# Ethernet.net
KiCad netlist of a schematic drawn in Altium Designer
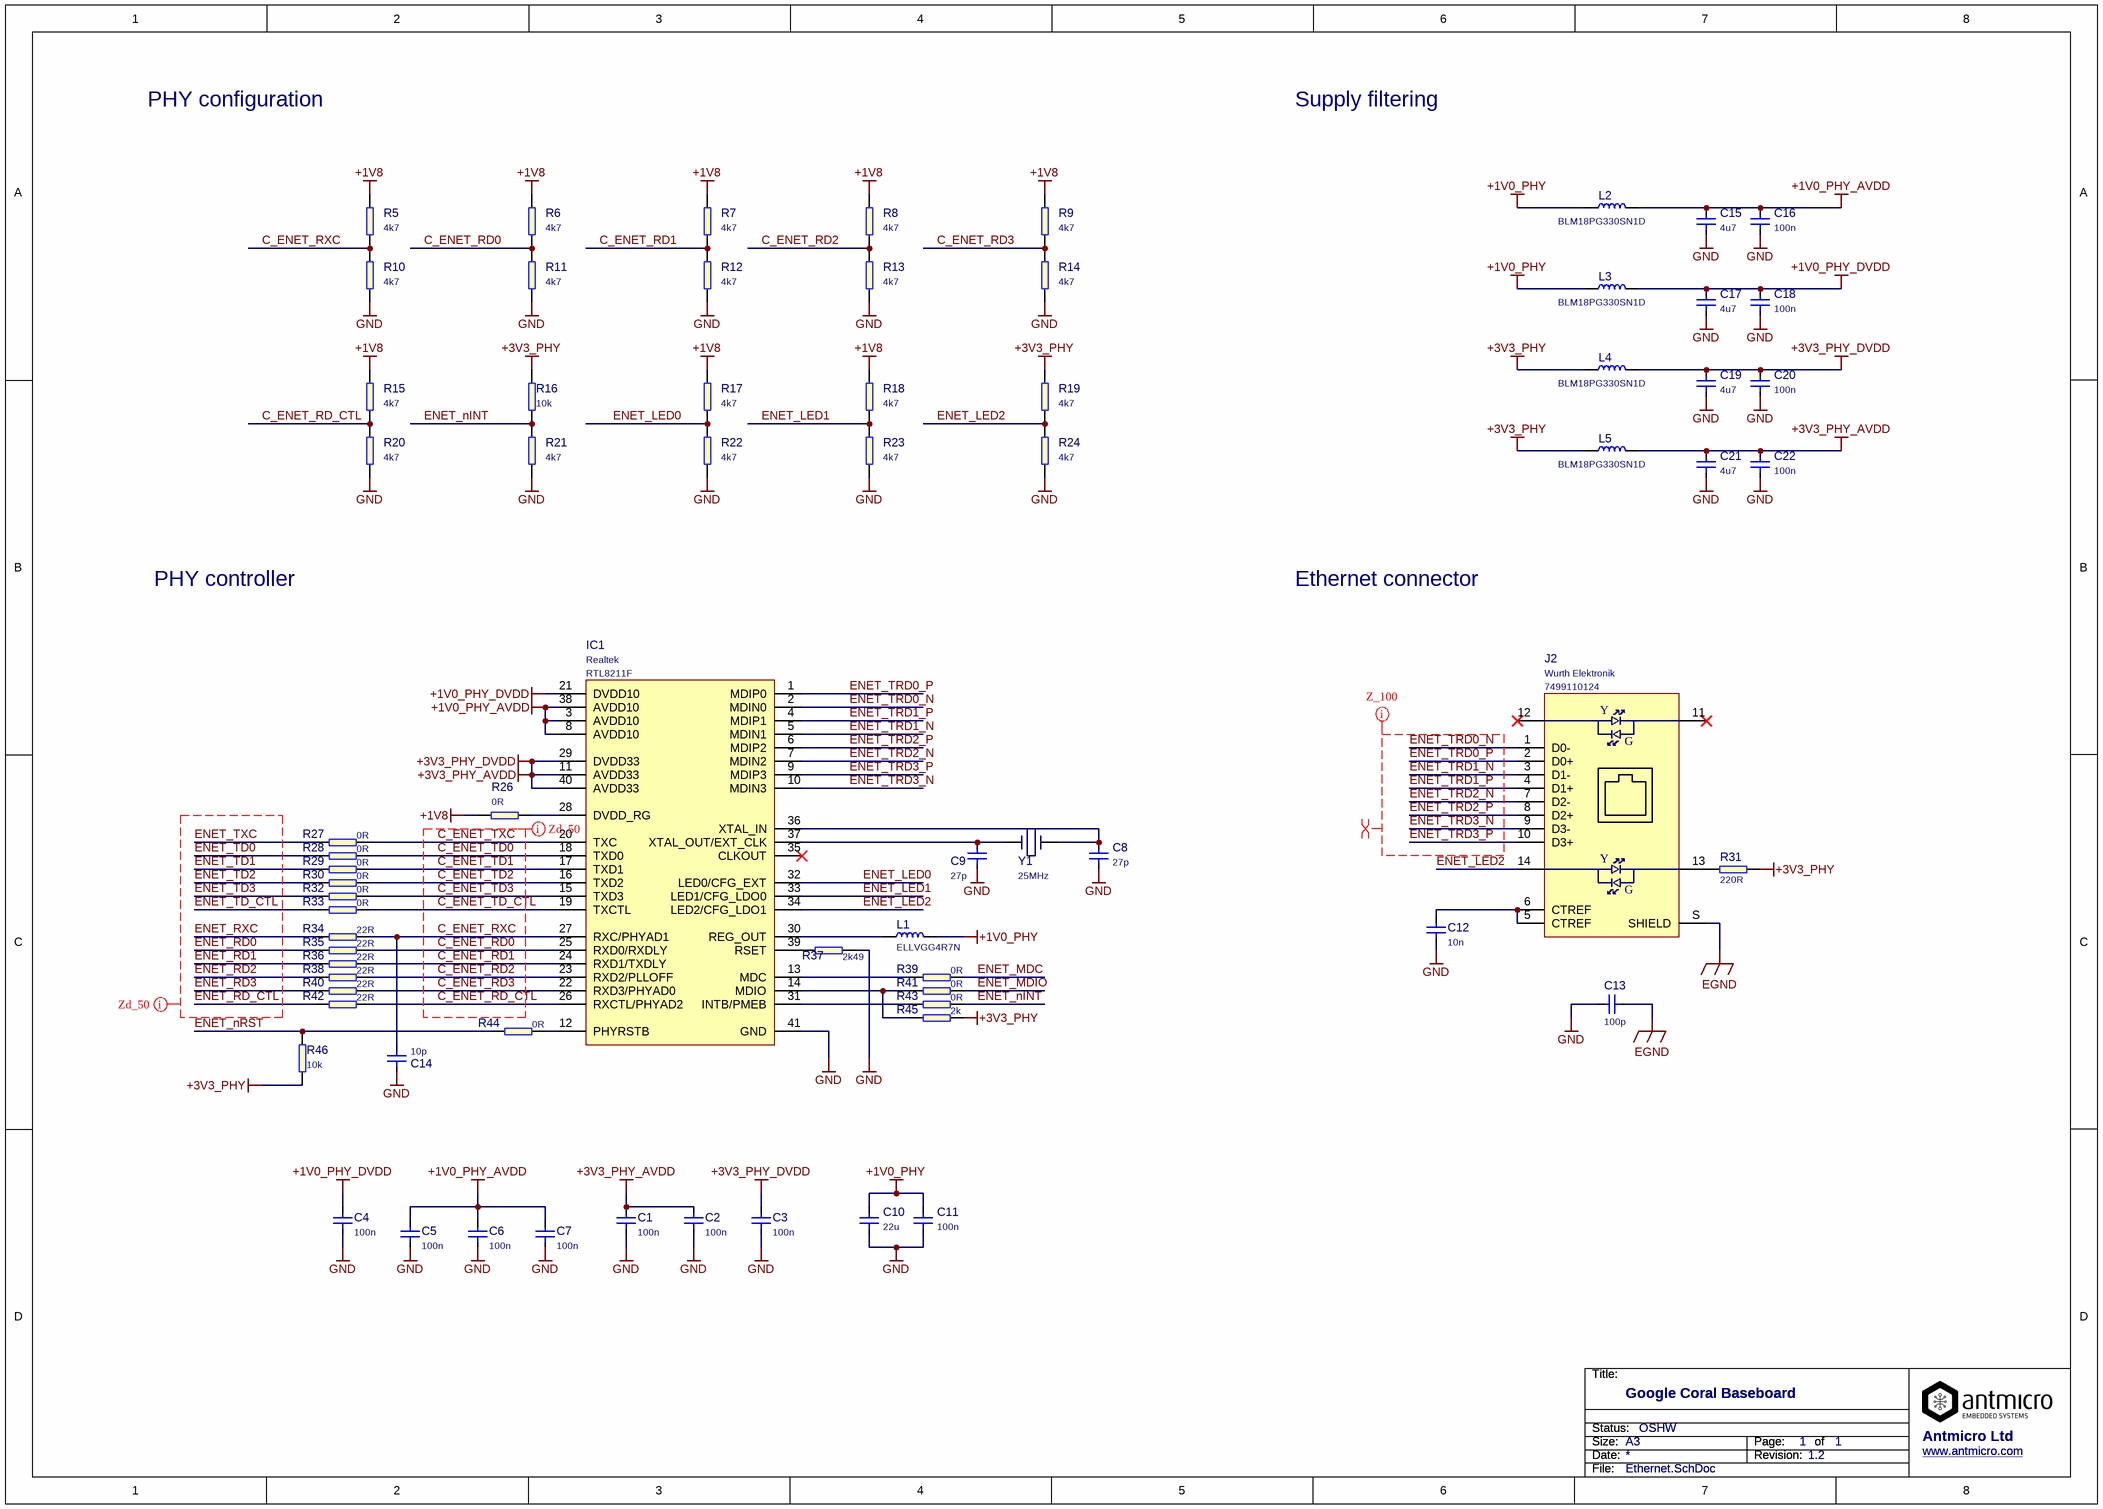
[diagram p0: Ethernet.SchDoc]

(export (version "E")
  (design (tool "Eeschema 10.0.6"))
  (components
    (comp (ref "C1")
      (value "100n")
      (footprint "C_0402")
      (description "MLCC SMT Capacitor 100nF 0402")
      (fields (field (name "PARTNUMBER") "C_100n_0402"))
      (libsource (lib "altium-import") (part "root_1_C_"))
    )
    (comp (ref "C2")
      (value "100n")
      (footprint "C_0402")
      (description "MLCC SMT Capacitor 100nF 0402")
      (fields (field (name "PARTNUMBER") "C_100n_0402"))
      (libsource (lib "altium-import") (part "root_1_C_"))
    )
    (comp (ref "C3")
      (value "100n")
      (footprint "C_0402")
      (description "MLCC SMT Capacitor 100nF 0402")
      (fields (field (name "PARTNUMBER") "C_100n_0402"))
      (libsource (lib "altium-import") (part "root_1_C_"))
    )
    (comp (ref "C4")
      (value "100n")
      (footprint "C_0402")
      (description "MLCC SMT Capacitor 100nF 0402")
      (fields (field (name "PARTNUMBER") "C_100n_0402"))
      (libsource (lib "altium-import") (part "root_1_C_"))
    )
    (comp (ref "C5")
      (value "100n")
      (footprint "C_0402")
      (description "MLCC SMT Capacitor 100nF 0402")
      (fields (field (name "PARTNUMBER") "C_100n_0402"))
      (libsource (lib "altium-import") (part "root_1_C_"))
    )
    (comp (ref "C6")
      (value "100n")
      (footprint "C_0402")
      (description "MLCC SMT Capacitor 100nF 0402")
      (fields (field (name "PARTNUMBER") "C_100n_0402"))
      (libsource (lib "altium-import") (part "root_1_C_"))
    )
    (comp (ref "C7")
      (value "100n")
      (footprint "C_0402")
      (description "MLCC SMT Capacitor 100nF 0402")
      (fields (field (name "PARTNUMBER") "C_100n_0402"))
      (libsource (lib "altium-import") (part "root_1_C_"))
    )
    (comp (ref "C8")
      (value "27p")
      (footprint "C_0402")
      (description "MLCC SMT Capacitor 27pF 0402")
      (fields (field (name "PARTNUMBER") "C_27p_0402"))
      (libsource (lib "altium-import") (part "root_1_C_"))
    )
    (comp (ref "C9")
      (value "27p")
      (footprint "C_0402")
      (description "MLCC SMT Capacitor 27pF 0402")
      (fields (field (name "PARTNUMBER") "C_27p_0402"))
      (libsource (lib "altium-import") (part "root_1_C_"))
    )
    (comp (ref "C10")
      (value "22u")
      (footprint "1210")
      (description "MLCC SMT Capacitor 22uF 1210")
      (fields (field (name "PARTNUMBER") "C_22u_1210"))
      (libsource (lib "altium-import") (part "root_1_C_"))
    )
    (comp (ref "C11")
      (value "100n")
      (footprint "C_0402")
      (description "MLCC SMT Capacitor 100nF 0402")
      (fields (field (name "PARTNUMBER") "C_100n_0402"))
      (libsource (lib "altium-import") (part "root_1_C_"))
    )
    (comp (ref "C12")
      (value "10n")
      (footprint "0603")
      (description "MLCC SMT Capacitor 10nF 0603")
      (fields (field (name "PARTNUMBER") "C_10n_0603"))
      (libsource (lib "altium-import") (part "root_1_C_"))
    )
    (comp (ref "C13")
      (value "100p")
      (footprint "0603")
      (description "MLCC SMT Capacitor 100pF 0603")
      (fields (field (name "PARTNUMBER") "C_100p_0603"))
      (libsource (lib "altium-import") (part "root_2_C_"))
    )
    (comp (ref "C14")
      (value "10p")
      (footprint "C_0402")
      (description "MLCC SMT Capacitor 10pF 0402")
      (fields (field (name "PARTNUMBER") "C_10p_0402"))
      (libsource (lib "altium-import") (part "root_1_C_"))
    )
    (comp (ref "C15")
      (value "4u7")
      (footprint "0603")
      (description "MLCC SMT Capacitor 4u7F 0603")
      (fields (field (name "PARTNUMBER") "C_4u7_0603"))
      (libsource (lib "altium-import") (part "root_1_C_"))
    )
    (comp (ref "C16")
      (value "100n")
      (footprint "C_0402")
      (description "MLCC SMT Capacitor 100nF 0402")
      (fields (field (name "PARTNUMBER") "C_100n_0402"))
      (libsource (lib "altium-import") (part "root_1_C_"))
    )
    (comp (ref "C17")
      (value "4u7")
      (footprint "0603")
      (description "MLCC SMT Capacitor 4u7F 0603")
      (fields (field (name "PARTNUMBER") "C_4u7_0603"))
      (libsource (lib "altium-import") (part "root_1_C_"))
    )
    (comp (ref "C18")
      (value "100n")
      (footprint "C_0402")
      (description "MLCC SMT Capacitor 100nF 0402")
      (fields (field (name "PARTNUMBER") "C_100n_0402"))
      (libsource (lib "altium-import") (part "root_1_C_"))
    )
    (comp (ref "C19")
      (value "4u7")
      (footprint "0603")
      (description "MLCC SMT Capacitor 4u7F 0603")
      (fields (field (name "PARTNUMBER") "C_4u7_0603"))
      (libsource (lib "altium-import") (part "root_1_C_"))
    )
    (comp (ref "C20")
      (value "100n")
      (footprint "C_0402")
      (description "MLCC SMT Capacitor 100nF 0402")
      (fields (field (name "PARTNUMBER") "C_100n_0402"))
      (libsource (lib "altium-import") (part "root_1_C_"))
    )
    (comp (ref "C21")
      (value "4u7")
      (footprint "0603")
      (description "MLCC SMT Capacitor 4u7F 0603")
      (fields (field (name "PARTNUMBER") "C_4u7_0603"))
      (libsource (lib "altium-import") (part "root_1_C_"))
    )
    (comp (ref "C22")
      (value "100n")
      (footprint "C_0402")
      (description "MLCC SMT Capacitor 100nF 0402")
      (fields (field (name "PARTNUMBER") "C_100n_0402"))
      (libsource (lib "altium-import") (part "root_1_C_"))
    )
    (comp (ref "IC1")
      (value "RTL8211F")
      (footprint "RTL8211F")
      (description "Highly Integrated 10/100/1000m Ethernet Transceiver")
      (fields (field (name "MANUFACTURER") "Realtek"))
      (libsource (lib "altium-import") (part "root_0_RTL8211F_"))
    )
    (comp (ref "J2")
      (value "7499110124")
      (footprint "WE_7499110124")
      (description "LAN-Transformer WE-RJ45LAN 10/100/1000 BaseT")
      (fields (field (name "MANUFACTURER") "Wurth Elektronik"))
      (libsource (lib "altium-import") (part "root_0_WE_7499111447_"))
    )
    (comp (ref "L1")
      (value "ELLVGG4R7N")
      (footprint "ELLVGG4R7N")
      (fields
        (field (name "MANUFACTURER") "PANASONIC ELECTRONIC COMPONENTS\r\n    ELLVGG4R7N \r\n    PANASONIC ELECTRONIC COMPONENTS")
      )
      (libsource (lib "altium-import") (part "root_0_Inductor SMT_"))
    )
    (comp (ref "L2")
      (value "BLM18PG330SN1D")
      (footprint "0603")
      (description "MURATA 	BLM18PG330SN1D  FERRITE BEAD, 0.025OHM, 3A, 0603")
      (fields (field (name "MANUFACTURER") "MURATA"))
      (libsource (lib "altium-import") (part "root_0_Inductor SMT_"))
    )
    (comp (ref "L3")
      (value "BLM18PG330SN1D")
      (footprint "0603")
      (description "MURATA 	BLM18PG330SN1D  FERRITE BEAD, 0.025OHM, 3A, 0603")
      (fields (field (name "MANUFACTURER") "MURATA"))
      (libsource (lib "altium-import") (part "root_0_Inductor SMT_"))
    )
    (comp (ref "L4")
      (value "BLM18PG330SN1D")
      (footprint "0603")
      (description "MURATA 	BLM18PG330SN1D  FERRITE BEAD, 0.025OHM, 3A, 0603")
      (fields (field (name "MANUFACTURER") "MURATA"))
      (libsource (lib "altium-import") (part "root_0_Inductor SMT_"))
    )
    (comp (ref "L5")
      (value "BLM18PG330SN1D")
      (footprint "0603")
      (description "MURATA 	BLM18PG330SN1D  FERRITE BEAD, 0.025OHM, 3A, 0603")
      (fields (field (name "MANUFACTURER") "MURATA"))
      (libsource (lib "altium-import") (part "root_0_Inductor SMT_"))
    )
    (comp (ref "R5")
      (value "4k7")
      (footprint "0402")
      (description "SMT Resistor 4k7 0402")
      (fields (field (name "PARTNUMBER") "R_4k7_0402"))
      (libsource (lib "altium-import") (part "root_1_R_"))
    )
    (comp (ref "R6")
      (value "4k7")
      (footprint "0402")
      (description "SMT Resistor 4k7 0402")
      (fields (field (name "PARTNUMBER") "R_4k7_0402"))
      (libsource (lib "altium-import") (part "root_1_R_"))
    )
    (comp (ref "R7")
      (value "4k7")
      (footprint "0402")
      (description "SMT Resistor 4k7 0402")
      (fields (field (name "PARTNUMBER") "R_4k7_0402"))
      (libsource (lib "altium-import") (part "root_1_R_"))
    )
    (comp (ref "R8")
      (value "4k7")
      (footprint "0402")
      (description "SMT Resistor 4k7 0402")
      (fields (field (name "PARTNUMBER") "R_4k7_0402"))
      (libsource (lib "altium-import") (part "root_1_R_"))
    )
    (comp (ref "R9")
      (value "4k7")
      (footprint "0402")
      (description "SMT Resistor 4k7 0402")
      (fields (field (name "PARTNUMBER") "R_4k7_0402"))
      (libsource (lib "altium-import") (part "root_1_R_"))
    )
    (comp (ref "R10")
      (value "4k7")
      (footprint "0402")
      (description "SMT Resistor 4k7 0402")
      (fields (field (name "PARTNUMBER") "R_4k7_0402"))
      (libsource (lib "altium-import") (part "root_1_R_"))
    )
    (comp (ref "R11")
      (value "4k7")
      (footprint "0402")
      (description "SMT Resistor 4k7 0402")
      (fields (field (name "PARTNUMBER") "R_4k7_0402"))
      (libsource (lib "altium-import") (part "root_1_R_"))
    )
    (comp (ref "R12")
      (value "4k7")
      (footprint "0402")
      (description "SMT Resistor 4k7 0402")
      (fields (field (name "PARTNUMBER") "R_4k7_0402"))
      (libsource (lib "altium-import") (part "root_1_R_"))
    )
    (comp (ref "R13")
      (value "4k7")
      (footprint "0402")
      (description "SMT Resistor 4k7 0402")
      (fields (field (name "PARTNUMBER") "R_4k7_0402"))
      (libsource (lib "altium-import") (part "root_1_R_"))
    )
    (comp (ref "R14")
      (value "4k7")
      (footprint "0402")
      (description "SMT Resistor 4k7 0402")
      (fields (field (name "PARTNUMBER") "R_4k7_0402"))
      (libsource (lib "altium-import") (part "root_1_R_"))
    )
    (comp (ref "R15")
      (value "4k7")
      (footprint "0402")
      (description "SMT Resistor 4k7 0402")
      (fields (field (name "PARTNUMBER") "R_4k7_0402"))
      (libsource (lib "altium-import") (part "root_1_R_"))
    )
    (comp (ref "R16")
      (value "10k")
      (footprint "0402")
      (description "SMT Resistor 0402")
      (fields (field (name "PARTNUMBER") "R_10k_0402"))
      (libsource (lib "altium-import") (part "root_1_R_"))
    )
    (comp (ref "R17")
      (value "4k7")
      (footprint "0402")
      (description "SMT Resistor 4k7 0402")
      (fields (field (name "PARTNUMBER") "R_4k7_0402"))
      (libsource (lib "altium-import") (part "root_1_R_"))
    )
    (comp (ref "R18")
      (value "4k7")
      (footprint "0402")
      (description "SMT Resistor 4k7 0402")
      (fields (field (name "PARTNUMBER") "R_4k7_0402"))
      (libsource (lib "altium-import") (part "root_1_R_"))
    )
    (comp (ref "R19")
      (value "4k7")
      (footprint "0402")
      (description "SMT Resistor 4k7 0402")
      (fields (field (name "PARTNUMBER") "R_4k7_0402"))
      (libsource (lib "altium-import") (part "root_1_R_"))
    )
    (comp (ref "R20")
      (value "4k7")
      (footprint "0402")
      (description "SMT Resistor 4k7 0402")
      (fields (field (name "PARTNUMBER") "R_4k7_0402"))
      (libsource (lib "altium-import") (part "root_1_R_"))
    )
    (comp (ref "R21")
      (value "4k7")
      (footprint "0402")
      (description "SMT Resistor 4k7 0402")
      (fields (field (name "PARTNUMBER") "R_4k7_0402"))
      (libsource (lib "altium-import") (part "root_1_R_"))
    )
    (comp (ref "R22")
      (value "4k7")
      (footprint "0402")
      (description "SMT Resistor 4k7 0402")
      (fields (field (name "PARTNUMBER") "R_4k7_0402"))
      (libsource (lib "altium-import") (part "root_1_R_"))
    )
    (comp (ref "R23")
      (value "4k7")
      (footprint "0402")
      (description "SMT Resistor 4k7 0402")
      (fields (field (name "PARTNUMBER") "R_4k7_0402"))
      (libsource (lib "altium-import") (part "root_1_R_"))
    )
    (comp (ref "R24")
      (value "4k7")
      (footprint "0402")
      (description "SMT Resistor 4k7 0402")
      (fields (field (name "PARTNUMBER") "R_4k7_0402"))
      (libsource (lib "altium-import") (part "root_1_R_"))
    )
    (comp (ref "R26")
      (value "0R")
      (footprint "0402")
      (description "SMT Resistor 0402")
      (fields (field (name "PARTNUMBER") "R_0R_0402"))
      (libsource (lib "altium-import") (part "root_0_R_"))
    )
    (comp (ref "R27")
      (value "0R")
      (footprint "0402")
      (description "SMT Resistor 0402")
      (fields (field (name "PARTNUMBER") "R_0R_0402"))
      (libsource (lib "altium-import") (part "root_0_R_"))
    )
    (comp (ref "R28")
      (value "0R")
      (footprint "0402")
      (description "SMT Resistor 0402")
      (fields (field (name "PARTNUMBER") "R_0R_0402"))
      (libsource (lib "altium-import") (part "root_0_R_"))
    )
    (comp (ref "R29")
      (value "0R")
      (footprint "0402")
      (description "SMT Resistor 0402")
      (fields (field (name "PARTNUMBER") "R_0R_0402"))
      (libsource (lib "altium-import") (part "root_0_R_"))
    )
    (comp (ref "R30")
      (value "0R")
      (footprint "0402")
      (description "SMT Resistor 0402")
      (fields (field (name "PARTNUMBER") "R_0R_0402"))
      (libsource (lib "altium-import") (part "root_0_R_"))
    )
    (comp (ref "R31")
      (value "220R")
      (footprint "0402")
      (description "SMT Resistor 220R 0402")
      (fields (field (name "PARTNUMBER") "R_220R_0402"))
      (libsource (lib "altium-import") (part "root_0_R_"))
    )
    (comp (ref "R32")
      (value "0R")
      (footprint "0402")
      (description "SMT Resistor 0402")
      (fields (field (name "PARTNUMBER") "R_0R_0402"))
      (libsource (lib "altium-import") (part "root_0_R_"))
    )
    (comp (ref "R33")
      (value "0R")
      (footprint "0402")
      (description "SMT Resistor 0402")
      (fields (field (name "PARTNUMBER") "R_0R_0402"))
      (libsource (lib "altium-import") (part "root_0_R_"))
    )
    (comp (ref "R34")
      (value "22R")
      (footprint "0402")
      (description "SMT Resistor 22R 0402")
      (fields (field (name "PARTNUMBER") "R_22R_0402"))
      (libsource (lib "altium-import") (part "root_0_R_"))
    )
    (comp (ref "R35")
      (value "22R")
      (footprint "0402")
      (description "SMT Resistor 22R 0402")
      (fields (field (name "PARTNUMBER") "R_22R_0402"))
      (libsource (lib "altium-import") (part "root_0_R_"))
    )
    (comp (ref "R36")
      (value "22R")
      (footprint "0402")
      (description "SMT Resistor 22R 0402")
      (fields (field (name "PARTNUMBER") "R_22R_0402"))
      (libsource (lib "altium-import") (part "root_0_R_"))
    )
    (comp (ref "R37")
      (value "2k49")
      (footprint "0603")
      (description "SMT Resistor 2k49 0603 1%")
      (fields (field (name "PARTNUMBER") "R_2k49_0603_1%"))
      (libsource (lib "altium-import") (part "root_0_R_"))
    )
    (comp (ref "R38")
      (value "22R")
      (footprint "0402")
      (description "SMT Resistor 22R 0402")
      (fields (field (name "PARTNUMBER") "R_22R_0402"))
      (libsource (lib "altium-import") (part "root_0_R_"))
    )
    (comp (ref "R39")
      (value "0R")
      (footprint "0402")
      (description "SMT Resistor 0402")
      (fields (field (name "PARTNUMBER") "R_0R_0402"))
      (libsource (lib "altium-import") (part "root_0_R_"))
    )
    (comp (ref "R40")
      (value "22R")
      (footprint "0402")
      (description "SMT Resistor 22R 0402")
      (fields (field (name "PARTNUMBER") "R_22R_0402"))
      (libsource (lib "altium-import") (part "root_0_R_"))
    )
    (comp (ref "R41")
      (value "0R")
      (footprint "0402")
      (description "SMT Resistor 0402")
      (fields (field (name "PARTNUMBER") "R_0R_0402"))
      (libsource (lib "altium-import") (part "root_0_R_"))
    )
    (comp (ref "R42")
      (value "22R")
      (footprint "0402")
      (description "SMT Resistor 22R 0402")
      (fields (field (name "PARTNUMBER") "R_22R_0402"))
      (libsource (lib "altium-import") (part "root_0_R_"))
    )
    (comp (ref "R43")
      (value "0R")
      (footprint "0402")
      (description "SMT Resistor 0402")
      (fields (field (name "PARTNUMBER") "R_0R_0402"))
      (libsource (lib "altium-import") (part "root_0_R_"))
    )
    (comp (ref "R44")
      (value "0R")
      (footprint "0402")
      (description "SMT Resistor 0402")
      (fields (field (name "PARTNUMBER") "R_0R_0402"))
      (libsource (lib "altium-import") (part "root_0_R_"))
    )
    (comp (ref "R45")
      (value "2k")
      (footprint "0402")
      (description "SMT Resistor 2k 0402")
      (fields (field (name "PARTNUMBER") "R_2k_0402"))
      (libsource (lib "altium-import") (part "root_0_R_"))
    )
    (comp (ref "R46")
      (value "10k")
      (footprint "0402")
      (description "SMT Resistor 0402")
      (fields (field (name "PARTNUMBER") "R_10k_0402"))
      (libsource (lib "altium-import") (part "root_1_R_"))
    )
    (comp (ref "Y1")
      (value "25MHz")
      (footprint "TXC_7A")
      (description "CRYSTAL, 25.000MHZ")
      (fields (field (name "PARTNUMBER") "CRYSTAL_25MHz_SMD_TXC") (field (name "MANUFACTURER") "TXC"))
      (libsource (lib "altium-import") (part "root_0_CRYSTAL_"))
    )
  )
  (nets
    (net (code "1") (name "+1V0_PHY") (class "Default")
      (node (ref "C10") (pin "2") (pinfunction "2_2") (pintype "passive"))
      (node (ref "C11") (pin "2") (pinfunction "2_2") (pintype "passive"))
      (node (ref "L1") (pin "2") (pintype "passive"))
      (node (ref "L2") (pin "1") (pintype "passive"))
      (node (ref "L3") (pin "1") (pintype "passive"))
    )
    (net (code "2") (name "+1V0_PHY_AVDD") (class "Default")
      (node (ref "C15") (pin "2") (pinfunction "2_2") (pintype "passive"))
      (node (ref "C16") (pin "2") (pinfunction "2_2") (pintype "passive"))
      (node (ref "C5") (pin "2") (pinfunction "2_2") (pintype "passive"))
      (node (ref "C6") (pin "2") (pinfunction "2_2") (pintype "passive"))
      (node (ref "C7") (pin "2") (pinfunction "2_2") (pintype "passive"))
      (node (ref "IC1") (pin "3") (pinfunction "AVDD10_3") (pintype "passive"))
      (node (ref "IC1") (pin "38") (pinfunction "AVDD10_38") (pintype "passive"))
      (node (ref "IC1") (pin "8") (pinfunction "AVDD10_8") (pintype "passive"))
      (node (ref "L2") (pin "2") (pintype "passive"))
    )
    (net (code "3") (name "+1V0_PHY_DVDD") (class "Default")
      (node (ref "C17") (pin "2") (pinfunction "2_2") (pintype "passive"))
      (node (ref "C18") (pin "2") (pinfunction "2_2") (pintype "passive"))
      (node (ref "C4") (pin "2") (pinfunction "2_2") (pintype "passive"))
      (node (ref "IC1") (pin "21") (pinfunction "DVDD10_21") (pintype "passive"))
      (node (ref "L3") (pin "2") (pintype "passive"))
    )
    (net (code "4") (name "+1V8") (class "Default")
      (node (ref "R15") (pin "2") (pintype "passive"))
      (node (ref "R17") (pin "2") (pintype "passive"))
      (node (ref "R18") (pin "2") (pintype "passive"))
      (node (ref "R26") (pin "1") (pintype "passive"))
      (node (ref "R5") (pin "2") (pintype "passive"))
      (node (ref "R6") (pin "2") (pintype "passive"))
      (node (ref "R7") (pin "2") (pintype "passive"))
      (node (ref "R8") (pin "2") (pintype "passive"))
      (node (ref "R9") (pin "2") (pintype "passive"))
    )
    (net (code "5") (name "+3V3_PHY") (class "Default")
      (node (ref "L4") (pin "1") (pintype "passive"))
      (node (ref "L5") (pin "1") (pintype "passive"))
      (node (ref "R16") (pin "2") (pintype "passive"))
      (node (ref "R19") (pin "2") (pintype "passive"))
      (node (ref "R31") (pin "2") (pintype "passive"))
      (node (ref "R45") (pin "2") (pintype "passive"))
      (node (ref "R46") (pin "1") (pintype "passive"))
    )
    (net (code "6") (name "+3V3_PHY_AVDD") (class "Default")
      (node (ref "C1") (pin "2") (pinfunction "2_2") (pintype "passive"))
      (node (ref "C19") (pin "2") (pinfunction "2_2") (pintype "passive"))
      (node (ref "C2") (pin "2") (pinfunction "2_2") (pintype "passive"))
      (node (ref "C20") (pin "2") (pinfunction "2_2") (pintype "passive"))
      (node (ref "C21") (pin "2") (pinfunction "2_2") (pintype "passive"))
      (node (ref "C22") (pin "2") (pinfunction "2_2") (pintype "passive"))
      (node (ref "C3") (pin "2") (pinfunction "2_2") (pintype "passive"))
      (node (ref "IC1") (pin "11") (pinfunction "AVDD33_11") (pintype "passive"))
      (node (ref "IC1") (pin "29") (pinfunction "DVDD33_29") (pintype "passive"))
      (node (ref "IC1") (pin "40") (pinfunction "AVDD33_40") (pintype "passive"))
      (node (ref "L4") (pin "2") (pintype "passive"))
      (node (ref "L5") (pin "2") (pintype "passive"))
    )
    (net (code "7") (name "/C_ENET_RD0") (class "Default")
      (node (ref "IC1") (pin "25") (pinfunction "RXD0/RXDLY_25") (pintype "passive"))
      (node (ref "R11") (pin "2") (pintype "passive"))
      (node (ref "R35") (pin "2") (pintype "passive"))
      (node (ref "R6") (pin "1") (pintype "passive"))
    )
    (net (code "8") (name "/C_ENET_RD1") (class "Default")
      (node (ref "IC1") (pin "24") (pinfunction "RXD1/TXDLY_24") (pintype "passive"))
      (node (ref "R12") (pin "2") (pintype "passive"))
      (node (ref "R36") (pin "2") (pintype "passive"))
      (node (ref "R7") (pin "1") (pintype "passive"))
    )
    (net (code "9") (name "/C_ENET_RD2") (class "Default")
      (node (ref "IC1") (pin "23") (pinfunction "RXD2/PLLOFF_23") (pintype "passive"))
      (node (ref "R13") (pin "2") (pintype "passive"))
      (node (ref "R38") (pin "2") (pintype "passive"))
      (node (ref "R8") (pin "1") (pintype "passive"))
    )
    (net (code "10") (name "/C_ENET_RD3") (class "Default")
      (node (ref "IC1") (pin "22") (pinfunction "RXD3/PHYAD0_22") (pintype "passive"))
      (node (ref "R14") (pin "2") (pintype "passive"))
      (node (ref "R40") (pin "2") (pintype "passive"))
      (node (ref "R9") (pin "1") (pintype "passive"))
    )
    (net (code "11") (name "/C_ENET_RD_CTL") (class "Default")
      (node (ref "IC1") (pin "26") (pinfunction "RXCTL/PHYAD2_26") (pintype "passive"))
      (node (ref "R15") (pin "1") (pintype "passive"))
      (node (ref "R20") (pin "2") (pintype "passive"))
      (node (ref "R42") (pin "2") (pintype "passive"))
    )
    (net (code "12") (name "/C_ENET_RXC") (class "Default")
      (node (ref "C14") (pin "2") (pinfunction "2_2") (pintype "passive"))
      (node (ref "IC1") (pin "27") (pinfunction "RXC/PHYAD1_27") (pintype "passive"))
      (node (ref "R10") (pin "2") (pintype "passive"))
      (node (ref "R34") (pin "2") (pintype "passive"))
      (node (ref "R5") (pin "1") (pintype "passive"))
    )
    (net (code "13") (name "/C_ENET_TD0") (class "Default")
      (node (ref "IC1") (pin "18") (pinfunction "TXD0_18") (pintype "passive"))
      (node (ref "R28") (pin "2") (pintype "passive"))
    )
    (net (code "14") (name "/C_ENET_TD1") (class "Default")
      (node (ref "IC1") (pin "17") (pinfunction "TXD1_17") (pintype "passive"))
      (node (ref "R29") (pin "2") (pintype "passive"))
    )
    (net (code "15") (name "/C_ENET_TD2") (class "Default")
      (node (ref "IC1") (pin "16") (pinfunction "TXD2_16") (pintype "passive"))
      (node (ref "R30") (pin "2") (pintype "passive"))
    )
    (net (code "16") (name "/C_ENET_TD3") (class "Default")
      (node (ref "IC1") (pin "15") (pinfunction "TXD3_15") (pintype "passive"))
      (node (ref "R32") (pin "2") (pintype "passive"))
    )
    (net (code "17") (name "/C_ENET_TD_CTL") (class "Default")
      (node (ref "IC1") (pin "19") (pinfunction "TXCTL_19") (pintype "passive"))
      (node (ref "R33") (pin "2") (pintype "passive"))
    )
    (net (code "18") (name "/C_ENET_TXC") (class "Default")
      (node (ref "IC1") (pin "20") (pinfunction "TXC_20") (pintype "passive"))
      (node (ref "R27") (pin "2") (pintype "passive"))
    )
    (net (code "19") (name "/ENET_LED0") (class "Default")
      (node (ref "IC1") (pin "32") (pinfunction "LED0/CFG_EXT_32") (pintype "passive"))
      (node (ref "R17") (pin "1") (pintype "passive"))
      (node (ref "R22") (pin "2") (pintype "passive"))
    )
    (net (code "20") (name "/ENET_LED1") (class "Default")
      (node (ref "IC1") (pin "33") (pinfunction "LED1/CFG_LDO0_33") (pintype "passive"))
      (node (ref "R18") (pin "1") (pintype "passive"))
      (node (ref "R23") (pin "2") (pintype "passive"))
    )
    (net (code "21") (name "/ENET_LED2") (class "Default")
      (node (ref "IC1") (pin "34") (pinfunction "LED2/CFG_LDO1_34") (pintype "passive"))
      (node (ref "J2") (pin "14") (pinfunction "14_14") (pintype "passive"))
      (node (ref "R19") (pin "1") (pintype "passive"))
      (node (ref "R24") (pin "2") (pintype "passive"))
    )
    (net (code "22") (name "/ENET_MDC") (class "Default") (node (ref "R39") (pin "2") (pintype "passive")))
    (net (code "23") (name "/ENET_MDIO") (class "Default") (node (ref "R41") (pin "2") (pintype "passive")))
    (net (code "24") (name "/ENET_RD0") (class "Default") (node (ref "R35") (pin "1") (pintype "passive")))
    (net (code "25") (name "/ENET_RD1") (class "Default") (node (ref "R36") (pin "1") (pintype "passive")))
    (net (code "26") (name "/ENET_RD2") (class "Default") (node (ref "R38") (pin "1") (pintype "passive")))
    (net (code "27") (name "/ENET_RD3") (class "Default") (node (ref "R40") (pin "1") (pintype "passive")))
    (net (code "28") (name "/ENET_RD_CTL") (class "Default") (node (ref "R42") (pin "1") (pintype "passive")))
    (net (code "29") (name "/ENET_RXC") (class "Default") (node (ref "R34") (pin "1") (pintype "passive")))
    (net (code "30") (name "/ENET_TD0") (class "Default") (node (ref "R28") (pin "1") (pintype "passive")))
    (net (code "31") (name "/ENET_TD1") (class "Default") (node (ref "R29") (pin "1") (pintype "passive")))
    (net (code "32") (name "/ENET_TD2") (class "Default") (node (ref "R30") (pin "1") (pintype "passive")))
    (net (code "33") (name "/ENET_TD3") (class "Default") (node (ref "R32") (pin "1") (pintype "passive")))
    (net (code "34") (name "/ENET_TD_CTL") (class "Default") (node (ref "R33") (pin "1") (pintype "passive")))
    (net (code "35") (name "/ENET_TRD0_N") (class "Default")
      (node (ref "IC1") (pin "2") (pinfunction "MDIN0_2") (pintype "passive"))
      (node (ref "J2") (pin "1") (pinfunction "D0-_1") (pintype "passive"))
    )
    (net (code "36") (name "/ENET_TRD0_P") (class "Default")
      (node (ref "IC1") (pin "1") (pinfunction "MDIP0_1") (pintype "passive"))
      (node (ref "J2") (pin "2") (pinfunction "D0+_2") (pintype "passive"))
    )
    (net (code "37") (name "/ENET_TRD1_N") (class "Default")
      (node (ref "IC1") (pin "5") (pinfunction "MDIN1_5") (pintype "passive"))
      (node (ref "J2") (pin "3") (pinfunction "D1-_3") (pintype "passive"))
    )
    (net (code "38") (name "/ENET_TRD1_P") (class "Default")
      (node (ref "IC1") (pin "4") (pinfunction "MDIP1_4") (pintype "passive"))
      (node (ref "J2") (pin "4") (pinfunction "D1+_4") (pintype "passive"))
    )
    (net (code "39") (name "/ENET_TRD2_N") (class "Default")
      (node (ref "IC1") (pin "7") (pinfunction "MDIN2_7") (pintype "passive"))
      (node (ref "J2") (pin "7") (pinfunction "D2-_7") (pintype "passive"))
    )
    (net (code "40") (name "/ENET_TRD2_P") (class "Default")
      (node (ref "IC1") (pin "6") (pinfunction "MDIP2_6") (pintype "passive"))
      (node (ref "J2") (pin "8") (pinfunction "D2+_8") (pintype "passive"))
    )
    (net (code "41") (name "/ENET_TRD3_N") (class "Default")
      (node (ref "IC1") (pin "10") (pinfunction "MDIN3_10") (pintype "passive"))
      (node (ref "J2") (pin "9") (pinfunction "D3-_9") (pintype "passive"))
    )
    (net (code "42") (name "/ENET_TRD3_P") (class "Default")
      (node (ref "IC1") (pin "9") (pinfunction "MDIP3_9") (pintype "passive"))
      (node (ref "J2") (pin "10") (pinfunction "D3+_10") (pintype "passive"))
    )
    (net (code "43") (name "/ENET_TXC") (class "Default") (node (ref "R27") (pin "1") (pintype "passive")))
    (net (code "44") (name "/ENET_nINT") (class "Default")
      (node (ref "R16") (pin "1") (pintype "passive"))
      (node (ref "R21") (pin "2") (pintype "passive"))
      (node (ref "R43") (pin "2") (pintype "passive"))
    )
    (net (code "45") (name "/ENET_nRST") (class "Default")
      (node (ref "R44") (pin "1") (pintype "passive"))
      (node (ref "R46") (pin "2") (pintype "passive"))
    )
    (net (code "46") (name "EGND") (class "Default")
      (node (ref "C13") (pin "1") (pinfunction "1_1") (pintype "passive"))
      (node (ref "J2") (pin "S") (pinfunction "SHIELD_S") (pintype "passive"))
    )
    (net (code "47") (name "GND") (class "Default")
      (node (ref "C1") (pin "1") (pinfunction "1_1") (pintype "passive"))
      (node (ref "C10") (pin "1") (pinfunction "1_1") (pintype "passive"))
      (node (ref "C11") (pin "1") (pinfunction "1_1") (pintype "passive"))
      (node (ref "C12") (pin "1") (pinfunction "1_1") (pintype "passive"))
      (node (ref "C13") (pin "2") (pinfunction "2_2") (pintype "passive"))
      (node (ref "C14") (pin "1") (pinfunction "1_1") (pintype "passive"))
      (node (ref "C15") (pin "1") (pinfunction "1_1") (pintype "passive"))
      (node (ref "C16") (pin "1") (pinfunction "1_1") (pintype "passive"))
      (node (ref "C17") (pin "1") (pinfunction "1_1") (pintype "passive"))
      (node (ref "C18") (pin "1") (pinfunction "1_1") (pintype "passive"))
      (node (ref "C19") (pin "1") (pinfunction "1_1") (pintype "passive"))
      (node (ref "C2") (pin "1") (pinfunction "1_1") (pintype "passive"))
      (node (ref "C20") (pin "1") (pinfunction "1_1") (pintype "passive"))
      (node (ref "C21") (pin "1") (pinfunction "1_1") (pintype "passive"))
      (node (ref "C22") (pin "1") (pinfunction "1_1") (pintype "passive"))
      (node (ref "C3") (pin "1") (pinfunction "1_1") (pintype "passive"))
      (node (ref "C4") (pin "1") (pinfunction "1_1") (pintype "passive"))
      (node (ref "C5") (pin "1") (pinfunction "1_1") (pintype "passive"))
      (node (ref "C6") (pin "1") (pinfunction "1_1") (pintype "passive"))
      (node (ref "C7") (pin "1") (pinfunction "1_1") (pintype "passive"))
      (node (ref "C8") (pin "1") (pinfunction "1_1") (pintype "passive"))
      (node (ref "C9") (pin "1") (pinfunction "1_1") (pintype "passive"))
      (node (ref "IC1") (pin "41") (pinfunction "GND_41") (pintype "passive"))
      (node (ref "R10") (pin "1") (pintype "passive"))
      (node (ref "R11") (pin "1") (pintype "passive"))
      (node (ref "R12") (pin "1") (pintype "passive"))
      (node (ref "R13") (pin "1") (pintype "passive"))
      (node (ref "R14") (pin "1") (pintype "passive"))
      (node (ref "R20") (pin "1") (pintype "passive"))
      (node (ref "R21") (pin "1") (pintype "passive"))
      (node (ref "R22") (pin "1") (pintype "passive"))
      (node (ref "R23") (pin "1") (pintype "passive"))
      (node (ref "R24") (pin "1") (pintype "passive"))
      (node (ref "R37") (pin "2") (pintype "passive"))
    )
    (net (code "48") (name "Net-(C12-Pad2)") (class "Default")
      (node (ref "C12") (pin "2") (pinfunction "2_2") (pintype "passive"))
      (node (ref "J2") (pin "5") (pinfunction "CTREF_5") (pintype "passive"))
      (node (ref "J2") (pin "6") (pinfunction "CTREF_6") (pintype "passive"))
    )
    (net (code "49") (name "Net-(IC1-DVDD_RG)") (class "Default")
      (node (ref "IC1") (pin "28") (pinfunction "DVDD_RG_28") (pintype "passive"))
      (node (ref "R26") (pin "2") (pintype "passive"))
    )
    (net (code "50") (name "Net-(IC1-INTB{slash}PMEB)") (class "Default")
      (node (ref "IC1") (pin "31") (pinfunction "INTB/PMEB_31") (pintype "passive"))
      (node (ref "R43") (pin "1") (pintype "passive"))
    )
    (net (code "51") (name "Net-(IC1-MDC)") (class "Default")
      (node (ref "IC1") (pin "13") (pinfunction "MDC_13") (pintype "passive"))
      (node (ref "R39") (pin "1") (pintype "passive"))
    )
    (net (code "52") (name "Net-(IC1-MDIO)") (class "Default")
      (node (ref "IC1") (pin "14") (pinfunction "MDIO_14") (pintype "passive"))
      (node (ref "R41") (pin "1") (pintype "passive"))
      (node (ref "R45") (pin "1") (pintype "passive"))
    )
    (net (code "53") (name "Net-(IC1-PHYRSTB)") (class "Default")
      (node (ref "IC1") (pin "12") (pinfunction "PHYRSTB_12") (pintype "passive"))
      (node (ref "R44") (pin "2") (pintype "passive"))
    )
    (net (code "54") (name "Net-(IC1-REG_OUT)") (class "Default")
      (node (ref "IC1") (pin "30") (pinfunction "REG_OUT_30") (pintype "passive"))
      (node (ref "L1") (pin "1") (pintype "passive"))
    )
    (net (code "55") (name "Net-(IC1-RSET)") (class "Default")
      (node (ref "IC1") (pin "39") (pinfunction "RSET_39") (pintype "passive"))
      (node (ref "R37") (pin "1") (pintype "passive"))
    )
    (net (code "56") (name "Net-(IC1-XTAL_IN)") (class "Default")
      (node (ref "C8") (pin "2") (pinfunction "2_2") (pintype "passive"))
      (node (ref "IC1") (pin "36") (pinfunction "XTAL_IN_36") (pintype "passive"))
      (node (ref "Y1") (pin "2") (pinfunction "2_2") (pintype "passive"))
    )
    (net (code "57") (name "Net-(IC1-XTAL_OUT{slash}EXT_CLK)") (class "Default")
      (node (ref "C9") (pin "2") (pinfunction "2_2") (pintype "passive"))
      (node (ref "IC1") (pin "37") (pinfunction "XTAL_OUT/EXT_CLK_37") (pintype "passive"))
      (node (ref "Y1") (pin "1") (pinfunction "1_1") (pintype "passive"))
    )
    (net (code "58") (name "Net-(J2-Pad13)") (class "Default")
      (node (ref "J2") (pin "13") (pinfunction "13_13") (pintype "passive"))
      (node (ref "R31") (pin "1") (pintype "passive"))
    )
    (net (code "59") (name "unconnected-(IC1-CLKOUT-Pad35)") (class "Default")
      (node (ref "IC1") (pin "35") (pinfunction "CLKOUT_35") (pintype "passive+no_connect"))
    )
    (net (code "60") (name "unconnected-(J2-Pad11)") (class "Default")
      (node (ref "J2") (pin "11") (pinfunction "11_11") (pintype "passive+no_connect"))
    )
    (net (code "61") (name "unconnected-(J2-Pad12)") (class "Default")
      (node (ref "J2") (pin "12") (pinfunction "12_12") (pintype "passive+no_connect"))
    )
  )
)
